# RS232-U4_U7.net
KiCad netlist of a schematic drawn in Altium Designer
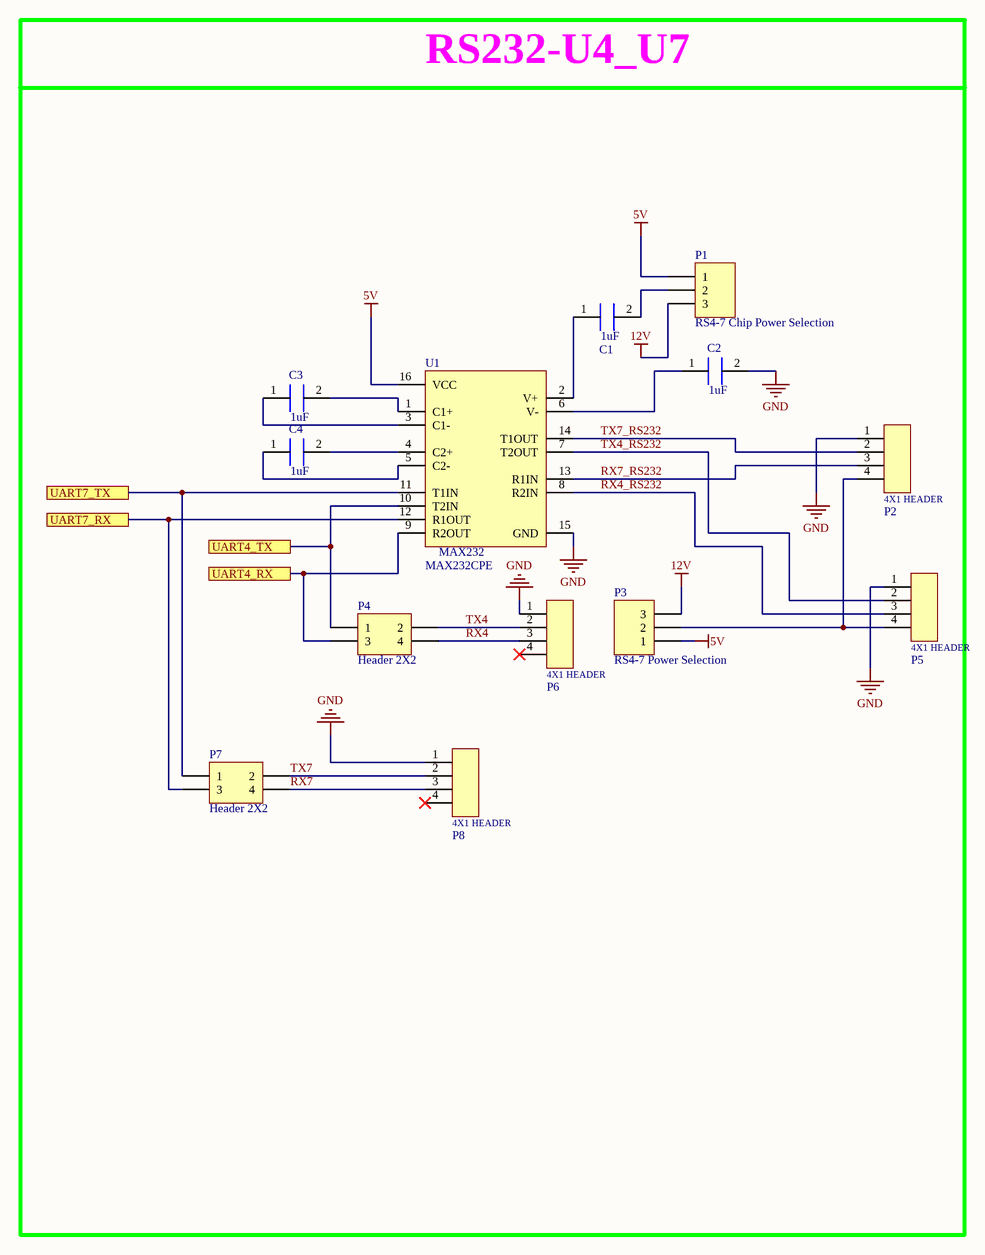
[diagram p0: RS232-U4_U7.SchDoc]

(export (version "E")
  (design (tool "Eeschema 10.0.6"))
  (components
    (comp (ref "C1")
      (value "CAP CER 1UF 25V X7R 0805")
      (footprint "C0805C105J3RAC7800")
      (description "Cap Ceramic 1uF 25V X7R 5% SMD 0805 125C Plastic T/R")
      (fields
        (field (name "MANUFACTURER") "KEMET")
        (field (name "MANUFACTURER PART NUMBER") "C0805C105J3RACTU")
      )
      (libsource (lib "Schlib1") (part "C0805C105J3RAC7800"))
    )
    (comp (ref "C2")
      (value "CAP CER 1UF 25V X7R 0805")
      (footprint "C0805C105J3RAC7800")
      (description "Cap Ceramic 1uF 25V X7R 5% SMD 0805 125C Plastic T/R")
      (fields
        (field (name "MANUFACTURER") "KEMET")
        (field (name "MANUFACTURER PART NUMBER") "C0805C105J3RACTU")
      )
      (libsource (lib "Schlib1") (part "C0805C105J3RAC7800"))
    )
    (comp (ref "C3")
      (value "CAP CER 1UF 25V X7R 0805")
      (footprint "C0805C105J3RAC7800")
      (description "Cap Ceramic 1uF 25V X7R 5% SMD 0805 125C Plastic T/R")
      (fields
        (field (name "MANUFACTURER") "KEMET")
        (field (name "MANUFACTURER PART NUMBER") "C0805C105J3RACTU")
      )
      (libsource (lib "Schlib1") (part "C0805C105J3RAC7800"))
    )
    (comp (ref "C4")
      (value "CAP CER 1UF 25V X7R 0805")
      (footprint "C0805C105J3RAC7800")
      (description "Cap Ceramic 1uF 25V X7R 5% SMD 0805 125C Plastic T/R")
      (fields
        (field (name "MANUFACTURER") "KEMET")
        (field (name "MANUFACTURER PART NUMBER") "C0805C105J3RACTU")
      )
      (libsource (lib "Schlib1") (part "C0805C105J3RAC7800"))
    )
    (comp (ref "P1")
      (value "RS4-7 Chip Power Selection")
      (footprint "HDR1X3")
      (description "Header, 3-Pin")
      (fields (field (name "PUBLISHER") "Altium Limited"))
      (libsource (lib "") (part "Header 3_1"))
    )
    (comp (ref "P2")
      (value "WIRE-TO BOARD HEADER, 2.5MM, 4 C")
      (footprint "51125-04-0200-01")
      (description "RS7 Port")
      (fields
        (field (name "MANUFACTURER") "CNC Tech")
        (field (name "MANUFACTURER PART NUMBER") "51125-04-0200-01")
      )
      (libsource (lib "Schlib1") (part "51125-04-0200-01"))
    )
    (comp (ref "P3")
      (value "RS4-7 Power Selection")
      (footprint "HDR1X3")
      (description "Header, 3-Pin")
      (fields (field (name "PUBLISHER") "Altium Limited"))
      (libsource (lib "Miscellaneous Connectors") (part "Header 3"))
    )
    (comp (ref "P4")
      (value "Header 2X2")
      (footprint "HDR2X2")
      (description "Header, 2-Pin, Dual row")
      (fields (field (name "PUBLISHER") "Altium Limited"))
      (libsource (lib "Miscellaneous Connectors") (part "Header 2X2"))
    )
    (comp (ref "P5")
      (value "WIRE-TO BOARD HEADER, 2.5MM, 4 C")
      (footprint "51125-04-0200-01")
      (description "Wire-to Board Header, 2.5MM, 4 C")
      (fields
        (field (name "MANUFACTURER") "CNC Tech")
        (field (name "MANUFACTURER PART NUMBER") "51125-04-0200-01")
      )
      (libsource (lib "Schlib1") (part "51125-04-0200-01"))
    )
    (comp (ref "P6")
      (value "WIRE-TO BOARD HEADER, 2.5MM, 4 C")
      (footprint "51125-04-0200-01")
      (description "Wire-to Board Header, 2.5MM, 4 C")
      (fields
        (field (name "MANUFACTURER") "CNC Tech")
        (field (name "MANUFACTURER PART NUMBER") "51125-04-0200-01")
      )
      (libsource (lib "Schlib1") (part "51125-04-0200-01"))
    )
    (comp (ref "P7")
      (value "Header 2X2")
      (footprint "HDR2X2")
      (description "Header, 2-Pin, Dual row")
      (fields (field (name "PUBLISHER") "Altium Limited"))
      (libsource (lib "Miscellaneous Connectors") (part "Header 2X2"))
    )
    (comp (ref "P8")
      (value "WIRE-TO BOARD HEADER, 2.5MM, 4 C")
      (footprint "51125-04-0200-01")
      (description "Wire-to Board Header, 2.5MM, 4 C")
      (fields
        (field (name "MANUFACTURER") "CNC Tech")
        (field (name "MANUFACTURER PART NUMBER") "51125-04-0200-01")
      )
      (libsource (lib "Schlib1") (part "51125-04-0200-01"))
    )
    (comp (ref "U1")
      (value "MAX232CPE")
      (footprint "MAX232CPE")
      (description "MAX232 Series 120 kbps 5.5 V Through Hole RS-232 Transceiver - PDIP-16")
      (fields (field (name "MANUFACTURER") "Maxim") (field (name "MANUFACTURER PART NUMBER") "MAX232CPE+"))
      (libsource (lib "Schlib1") (part "MAX232CPE"))
    )
  )
  (nets
    (net (code "1") (name "/RX4") (class "Default")
      (node (ref "P4") (pin "4") (pinfunction "4_4") (pintype "passive"))
      (node (ref "P6") (pin "3") (pinfunction "7_3") (pintype "passive"))
    )
    (net (code "2") (name "/RX4_RS232") (class "Default")
      (node (ref "P5") (pin "3") (pinfunction "7_3") (pintype "passive"))
      (node (ref "U1") (pin "8") (pinfunction "R2IN_8") (pintype "passive"))
    )
    (net (code "3") (name "/RX7") (class "Default")
      (node (ref "P7") (pin "4") (pinfunction "4_4") (pintype "passive"))
      (node (ref "P8") (pin "3") (pinfunction "7_3") (pintype "passive"))
    )
    (net (code "4") (name "/RX7_RS232") (class "Default")
      (node (ref "P2") (pin "3") (pinfunction "7_3") (pintype "passive"))
      (node (ref "U1") (pin "13") (pinfunction "R1IN_13") (pintype "passive"))
    )
    (net (code "5") (name "/TX4") (class "Default")
      (node (ref "P4") (pin "2") (pinfunction "2_2") (pintype "passive"))
      (node (ref "P6") (pin "2") (pinfunction "8_2") (pintype "passive"))
    )
    (net (code "6") (name "/TX4_RS232") (class "Default")
      (node (ref "P5") (pin "2") (pinfunction "8_2") (pintype "passive"))
      (node (ref "U1") (pin "7") (pinfunction "T2OUT_7") (pintype "passive"))
    )
    (net (code "7") (name "/TX7") (class "Default")
      (node (ref "P7") (pin "2") (pinfunction "2_2") (pintype "passive"))
      (node (ref "P8") (pin "2") (pinfunction "8_2") (pintype "passive"))
    )
    (net (code "8") (name "/TX7_RS232") (class "Default")
      (node (ref "P2") (pin "2") (pinfunction "8_2") (pintype "passive"))
      (node (ref "U1") (pin "14") (pinfunction "T1OUT_14") (pintype "passive"))
    )
    (net (code "9") (name "/UART4_RX") (class "Default")
      (node (ref "P4") (pin "3") (pinfunction "3_3") (pintype "passive"))
      (node (ref "U1") (pin "9") (pinfunction "R2OUT_9") (pintype "passive"))
    )
    (net (code "10") (name "/UART4_TX") (class "Default")
      (node (ref "P4") (pin "1") (pinfunction "1_1") (pintype "passive"))
      (node (ref "U1") (pin "10") (pinfunction "T2IN_10") (pintype "passive"))
    )
    (net (code "11") (name "/UART7_RX") (class "Default")
      (node (ref "P7") (pin "3") (pinfunction "3_3") (pintype "passive"))
      (node (ref "U1") (pin "12") (pinfunction "R1OUT_12") (pintype "passive"))
    )
    (net (code "12") (name "/UART7_TX") (class "Default")
      (node (ref "P7") (pin "1") (pinfunction "1_1") (pintype "passive"))
      (node (ref "U1") (pin "11") (pinfunction "T1IN_11") (pintype "passive"))
    )
    (net (code "13") (name "5V") (class "Default")
      (node (ref "P1") (pin "1") (pinfunction "1_1") (pintype "passive"))
      (node (ref "P3") (pin "1") (pinfunction "1_1") (pintype "passive"))
      (node (ref "U1") (pin "16") (pinfunction "VCC_16") (pintype "passive"))
    )
    (net (code "14") (name "12V") (class "Default")
      (node (ref "P1") (pin "3") (pinfunction "3_3") (pintype "passive"))
      (node (ref "P3") (pin "3") (pinfunction "3_3") (pintype "passive"))
    )
    (net (code "15") (name "GND") (class "Default")
      (node (ref "C2") (pin "2") (pintype "passive"))
      (node (ref "P2") (pin "1") (pintype "passive"))
      (node (ref "P5") (pin "1") (pintype "passive"))
      (node (ref "P6") (pin "1") (pintype "passive"))
      (node (ref "P8") (pin "1") (pintype "passive"))
      (node (ref "U1") (pin "15") (pinfunction "GND_15") (pintype "passive"))
    )
    (net (code "16") (name "Net-(C1-Pad2)") (class "Default")
      (node (ref "C1") (pin "2") (pintype "passive"))
      (node (ref "P1") (pin "2") (pinfunction "2_2") (pintype "passive"))
    )
    (net (code "17") (name "Net-(P2-6)") (class "Default")
      (node (ref "P2") (pin "4") (pinfunction "6_4") (pintype "passive"))
      (node (ref "P3") (pin "2") (pinfunction "2_2") (pintype "passive"))
      (node (ref "P5") (pin "4") (pinfunction "6_4") (pintype "passive"))
    )
    (net (code "18") (name "Net-(U1-C1+)") (class "Default")
      (node (ref "C3") (pin "2") (pintype "passive"))
      (node (ref "U1") (pin "1") (pinfunction "C1+_1") (pintype "passive"))
    )
    (net (code "19") (name "Net-(U1-C1-)") (class "Default")
      (node (ref "C3") (pin "1") (pintype "passive"))
      (node (ref "U1") (pin "3") (pinfunction "C1-_3") (pintype "passive"))
    )
    (net (code "20") (name "Net-(U1-C2+)") (class "Default")
      (node (ref "C4") (pin "2") (pintype "passive"))
      (node (ref "U1") (pin "4") (pinfunction "C2+_4") (pintype "passive"))
    )
    (net (code "21") (name "Net-(U1-C2-)") (class "Default")
      (node (ref "C4") (pin "1") (pintype "passive"))
      (node (ref "U1") (pin "5") (pinfunction "C2-_5") (pintype "passive"))
    )
    (net (code "22") (name "Net-(U1-V+)") (class "Default")
      (node (ref "C1") (pin "1") (pintype "passive"))
      (node (ref "U1") (pin "2") (pinfunction "V+_2") (pintype "passive"))
    )
    (net (code "23") (name "Net-(U1-V-)") (class "Default")
      (node (ref "C2") (pin "1") (pintype "passive"))
      (node (ref "U1") (pin "6") (pinfunction "V-_6") (pintype "passive"))
    )
    (net (code "24") (name "unconnected-(P6-6-Pad4)") (class "Default")
      (node (ref "P6") (pin "4") (pinfunction "6_4") (pintype "passive+no_connect"))
    )
    (net (code "25") (name "unconnected-(P8-6-Pad4)") (class "Default")
      (node (ref "P8") (pin "4") (pinfunction "6_4") (pintype "passive+no_connect"))
    )
  )
)
